# Sheet_24V_PWR.net
KiCad netlist of a schematic drawn in Altium Designer
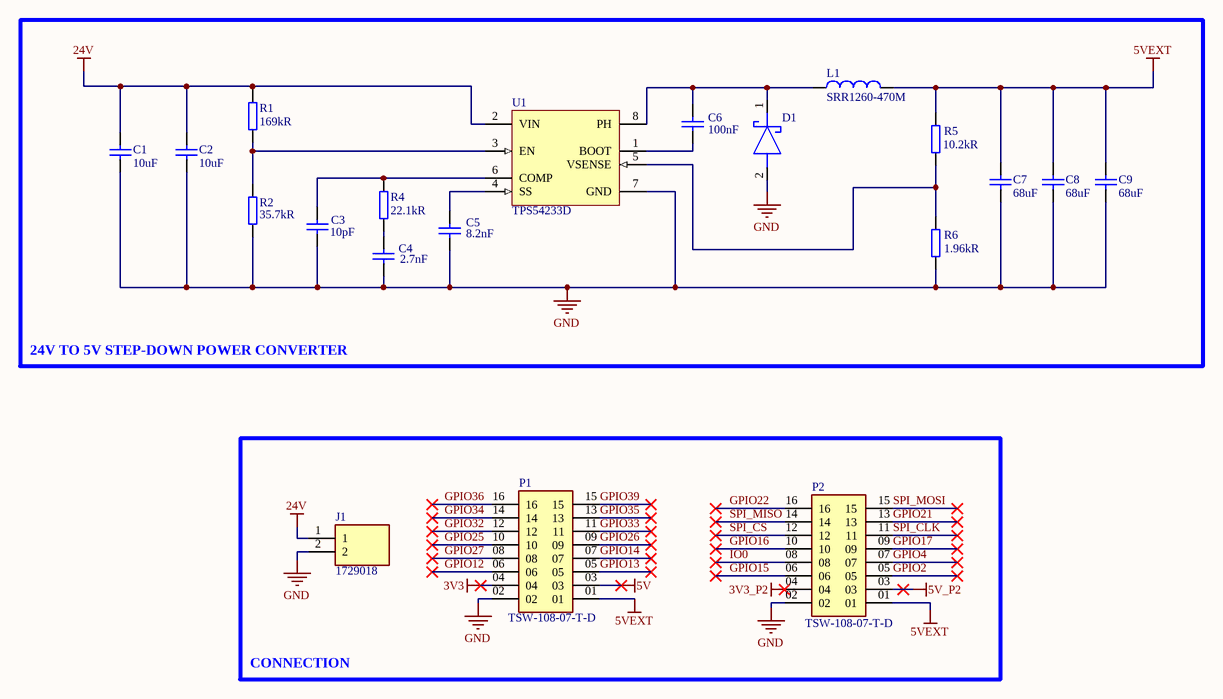
[diagram p0: Sheet_24V_PWR.SchDoc]

(export (version "E")
  (design (tool "Eeschema 10.0.6"))
  (components
    (comp (ref "C1")
      (value "C1210C106M5RACTU")
      (footprint "FP-C3225-250-0_4-IPC_A")
      (description "3225 C 10uF Ceramic Multilayer Capacitor; 50 V; +85degC; X7R Dielectric; +/-20%")
      (fields
        (field (name "MANUFACTURER") "KEMET")
        (field (name "CAPACITANCE") "10uF")
        (field (name "VOLTAGE") "50V")
      )
      (libsource (lib "Schlib1") (part "C1210C106M5RACTU"))
    )
    (comp (ref "C2")
      (value "C1210C106M5RACTU")
      (footprint "FP-C3225-250-0_4-IPC_A")
      (description "3225 C 10uF Ceramic Multilayer Capacitor; 50 V; +85degC; X7R Dielectric; +/-20%")
      (fields
        (field (name "MANUFACTURER") "KEMET")
        (field (name "CAPACITANCE") "10uF")
        (field (name "VOLTAGE") "50V")
      )
      (libsource (lib "Schlib1") (part "C1210C106M5RACTU"))
    )
    (comp (ref "C3")
      (value "C0805C100J5GACTU")
      (footprint "FP-C0805C-DN-IPC_A")
      (description "Cap Ceramic 10pF 50V C0G 5% SMD 0805 125C Plastic T/R")
      (fields
        (field (name "MANUFACTURER") "KEMET")
        (field (name "CAPACITANCE") "10pF")
        (field (name "TOLERANCE") "5%")
      )
      (libsource (lib "Schlib1") (part "C0805C100J5GACTU"))
    )
    (comp (ref "C4")
      (value "C2012C0G1H272J060AA")
      (footprint "FP-C2012-060-0_2-IPC_A")
      (description "Cap Ceramic 0.0027uF 50V C0G 5% SMD 0805 125C Paper T/R")
      (fields
        (field (name "MANUFACTURER") "TDK")
        (field (name "CAPACITANCE") "2.7nF")
        (field (name "TOLERANCE") "5%")
      )
      (libsource (lib "Schlib1") (part "C2012C0G1H272J060AA"))
    )
    (comp (ref "C5")
      (value "C0805C822K4RACTU")
      (footprint "FP-C0805C-DN-IPC_A")
      (description "Capacitor, Ceramic, 8.2nF, 16VDC, 10-% Tol, 10+% Tol, X7R-TC Code, -15, 15%-TC RoHS Compliant: Yes")
      (fields
        (field (name "MANUFACTURER") "KEMET")
        (field (name "CAPACITANCE") "8.2nF")
        (field (name "TOLERANCE") "10%")
      )
      (libsource (lib "Schlib1") (part "C0805C822K4RACTU"))
    )
    (comp (ref "C6")
      (value "C0805C104K8RACTU")
      (footprint "FP-C0805C-DN-IPC_A")
      (description "Cap Ceramic 0.1uF 10V X7R 10% SMD 0805 125°C Paper T/R")
      (fields
        (field (name "MANUFACTURER") "KEMET")
        (field (name "CAPACITANCE") "100nF")
        (field (name "TOLERANCE") "10%")
      )
      (libsource (lib "Schlib1") (part "C0805C104K8RACTU"))
    )
    (comp (ref "C7")
      (value "C3216X5R1A686M160AC")
      (footprint "FP-C3216-160-0_3-IPC_A")
      (description "C Series 1206 68 uF 10 V ±20 % Tolerance X5R SMT Multilayer Ceramic Capacitor")
      (fields
        (field (name "MANUFACTURER") "TDK")
        (field (name "CAPACITANCE") "68uF")
        (field (name "TOLERANCE") "20%")
      )
      (libsource (lib "Schlib1") (part "C3216X5R1A686M160AC"))
    )
    (comp (ref "C8")
      (value "C3216X5R1A686M160AC")
      (footprint "FP-C3216-160-0_3-IPC_A")
      (description "C Series 1206 68 uF 10 V ±20 % Tolerance X5R SMT Multilayer Ceramic Capacitor")
      (fields
        (field (name "MANUFACTURER") "TDK")
        (field (name "CAPACITANCE") "68uF")
        (field (name "TOLERANCE") "20%")
      )
      (libsource (lib "Schlib1") (part "C3216X5R1A686M160AC"))
    )
    (comp (ref "C9")
      (value "C3216X5R1A686M160AC")
      (footprint "FP-C3216-160-0_3-IPC_A")
      (description "C Series 1206 68 uF 10 V ±20 % Tolerance X5R SMT Multilayer Ceramic Capacitor")
      (fields
        (field (name "MANUFACTURER") "TDK")
        (field (name "CAPACITANCE") "68uF")
        (field (name "TOLERANCE") "20%")
      )
      (libsource (lib "Schlib1") (part "C3216X5R1A686M160AC"))
    )
    (comp (ref "D1")
      (value "SS2PH10-M3/84A")
      (footprint "DO-220AA")
      (description "DIODE SCHOTTKY 100V 2A DO220AA")
      (fields (field (name "MANUFACTURER") "Vishay"))
      (libsource (lib "Schlib1") (part "SS2PH10-M3/84A"))
    )
    (comp (ref "J1")
      (value "1729018")
      (footprint "1729018")
      (description "间距5mm 2pin 10A 300V 可拼接 螺钉式 直插")
      (fields (field (name "MANUFACTURER") "Phoenix Contact") (field (name "VOLTAGE") "300V"))
      (libsource (lib "Schlib1") (part "1729018"))
    )
    (comp (ref "L1")
      (value "SRR1260-470M")
      (footprint "SRR1260470M")
      (description "Inductor Power Shielded Wirewound 47uH 20% 100KHz 22Q-Factor Ferrite 2.6A 86mOhm DCR T/R")
      (fields (field (name "MANUFACTURER") "Bourns") (field (name "TOLERANCE") "20%"))
      (libsource (lib "Schlib1") (part "SRR1260-470M"))
    )
    (comp (ref "P1")
      (value "TSW-108-07-T-D")
      (footprint "SAMTEC_TSW-108-07-T-D")
      (description "Conn Unshrouded Header HDR 16 POS 2.54mm Solder ST Thru-Hole Bulk")
      (fields (field (name "MANUFACTURER") "Samtec"))
      (libsource (lib "Schlib1") (part "TSW-108-07-T-D"))
    )
    (comp (ref "P2")
      (value "TSW-108-07-T-D")
      (footprint "SAMTEC_TSW-108-07-T-D")
      (description "Conn Unshrouded Header HDR 16 POS 2.54mm Solder ST Thru-Hole Bulk")
      (fields (field (name "MANUFACTURER") "Samtec"))
      (libsource (lib "Schlib1") (part "TSW-108-07-T-D"))
    )
    (comp (ref "R1")
      (value "ERJ-6ENF1693V")
      (footprint "RESC2013X70X40LL20T20")
      (description "Res Thick Film 0805 169K Ohm 1% 1/8W ±100ppm/°C Molded SMD Punched Carrier T/R")
      (fields
        (field (name "MANUFACTURER") "Panasonic")
        (field (name "RESISTANCE") "169kR")
        (field (name "TOLERANCE") "1%")
      )
      (libsource (lib "Schlib1") (part "ERJ-6ENF1693V"))
    )
    (comp (ref "R2")
      (value "CR0805-FX-3572ELF")
      (footprint "RESC0805(2012)_L")
      (description "Res Thick Film 0805 35.7K Ohm 1% 1/8W 100ppm/C Molded SMD SMD Paper Tape on Plastic Reel")
      (fields
        (field (name "MANUFACTURER") "Bourns")
        (field (name "RESISTANCE") "35.7kR")
        (field (name "TOLERANCE") "1%")
      )
      (libsource (lib "Schlib1") (part "CR0805-FX-3572ELF"))
    )
    (comp (ref "R4")
      (value "CR0805-FX-2212ELF")
      (footprint "RESC2012X60N")
      (description "Res Thick Film 0805 22.1K Ohm 1% 1/8W ±100ppm/°C Molded SMD SMD Paper Tape on Plastic Reel")
      (fields
        (field (name "MANUFACTURER") "Bourns")
        (field (name "RESISTANCE") "22.1kR")
        (field (name "TOLERANCE") "1%")
      )
      (libsource (lib "Schlib1") (part "CR0805-FX-2212ELF"))
    )
    (comp (ref "R5")
      (value "CR0805-FX-1022ELF")
      (footprint "RESC2012X60N")
      (description "Res Thick Film 0805 10.2K Ohm 1% 1/8W ±100ppm/°C Molded SMD SMD Paper Tape on Plastic Reel")
      (fields
        (field (name "MANUFACTURER") "Bourns")
        (field (name "RESISTANCE") "10.2kR")
        (field (name "TOLERANCE") "1%")
      )
      (libsource (lib "Schlib1") (part "CR0805-FX-1022ELF"))
    )
    (comp (ref "R6")
      (value "CRCW08051K96FKEA")
      (footprint "RESC2013X50X30LL20T20")
      (description "Res Thick Film 0805 1.96K Ohm 1% 1/8W ±100ppm/°C Molded SMD SMD Paper T/R")
      (fields
        (field (name "MANUFACTURER") "Vishay")
        (field (name "RESISTANCE") "1.96kR")
        (field (name "TOLERANCE") "1%")
      )
      (libsource (lib "Schlib1") (part "CRCW08051K96FKEA"))
    )
    (comp (ref "U1")
      (value "TPS54233D")
      (footprint "D0008A_L")
      (description "3.5 to 28V Input, 2A, 300kHz Step-Down Converter with Eco-mode 8-SOIC -40 to 150")
      (fields (field (name "MANUFACTURER") "Texas Instruments"))
      (libsource (lib "Schlib1") (part "TPS54233D"))
    )
  )
  (nets
    (net (code "1") (name "/GPIO2") (class "Default")
      (node (ref "P2") (pin "05") (pinfunction "05_05") (pintype "passive+no_connect"))
    )
    (net (code "2") (name "/GPIO4") (class "Default")
      (node (ref "P2") (pin "07") (pinfunction "07_07") (pintype "passive+no_connect"))
    )
    (net (code "3") (name "/GPIO12") (class "Default")
      (node (ref "P1") (pin "06") (pinfunction "06_06") (pintype "passive+no_connect"))
    )
    (net (code "4") (name "/GPIO13") (class "Default")
      (node (ref "P1") (pin "05") (pinfunction "05_05") (pintype "passive+no_connect"))
    )
    (net (code "5") (name "/GPIO14") (class "Default")
      (node (ref "P1") (pin "07") (pinfunction "07_07") (pintype "passive+no_connect"))
    )
    (net (code "6") (name "/GPIO15") (class "Default")
      (node (ref "P2") (pin "06") (pinfunction "06_06") (pintype "passive+no_connect"))
    )
    (net (code "7") (name "/GPIO16") (class "Default")
      (node (ref "P2") (pin "10") (pinfunction "10_10") (pintype "passive+no_connect"))
    )
    (net (code "8") (name "/GPIO17") (class "Default")
      (node (ref "P2") (pin "09") (pinfunction "09_09") (pintype "passive+no_connect"))
    )
    (net (code "9") (name "/GPIO21") (class "Default")
      (node (ref "P2") (pin "13") (pinfunction "13_13") (pintype "passive+no_connect"))
    )
    (net (code "10") (name "/GPIO22") (class "Default")
      (node (ref "P2") (pin "16") (pinfunction "16_16") (pintype "passive+no_connect"))
    )
    (net (code "11") (name "/GPIO25") (class "Default")
      (node (ref "P1") (pin "10") (pinfunction "10_10") (pintype "passive+no_connect"))
    )
    (net (code "12") (name "/GPIO26") (class "Default")
      (node (ref "P1") (pin "09") (pinfunction "09_09") (pintype "passive+no_connect"))
    )
    (net (code "13") (name "/GPIO27") (class "Default")
      (node (ref "P1") (pin "08") (pinfunction "08_08") (pintype "passive+no_connect"))
    )
    (net (code "14") (name "/GPIO32") (class "Default")
      (node (ref "P1") (pin "12") (pinfunction "12_12") (pintype "passive+no_connect"))
    )
    (net (code "15") (name "/GPIO33") (class "Default")
      (node (ref "P1") (pin "11") (pinfunction "11_11") (pintype "passive+no_connect"))
    )
    (net (code "16") (name "/GPIO34") (class "Default")
      (node (ref "P1") (pin "14") (pinfunction "14_14") (pintype "passive+no_connect"))
    )
    (net (code "17") (name "/GPIO35") (class "Default")
      (node (ref "P1") (pin "13") (pinfunction "13_13") (pintype "passive+no_connect"))
    )
    (net (code "18") (name "/GPIO36") (class "Default")
      (node (ref "P1") (pin "16") (pinfunction "16_16") (pintype "passive+no_connect"))
    )
    (net (code "19") (name "/GPIO39") (class "Default")
      (node (ref "P1") (pin "15") (pinfunction "15_15") (pintype "passive+no_connect"))
    )
    (net (code "20") (name "/IO0") (class "Default")
      (node (ref "P2") (pin "08") (pinfunction "08_08") (pintype "passive+no_connect"))
    )
    (net (code "21") (name "/SPI_CLK") (class "Default")
      (node (ref "P2") (pin "11") (pinfunction "11_11") (pintype "passive+no_connect"))
    )
    (net (code "22") (name "/SPI_CS") (class "Default")
      (node (ref "P2") (pin "12") (pinfunction "12_12") (pintype "passive+no_connect"))
    )
    (net (code "23") (name "/SPI_MISO") (class "Default")
      (node (ref "P2") (pin "14") (pinfunction "14_14") (pintype "passive+no_connect"))
    )
    (net (code "24") (name "/SPI_MOSI") (class "Default")
      (node (ref "P2") (pin "15") (pinfunction "15_15") (pintype "passive+no_connect"))
    )
    (net (code "25") (name "3V3") (class "Default")
      (node (ref "P1") (pin "04") (pinfunction "04_04") (pintype "passive"))
    )
    (net (code "26") (name "3V3_P2") (class "Default")
      (node (ref "P2") (pin "04") (pinfunction "04_04") (pintype "passive"))
    )
    (net (code "27") (name "5V") (class "Default")
      (node (ref "P1") (pin "03") (pinfunction "03_03") (pintype "passive"))
    )
    (net (code "28") (name "5VEXT") (class "Default")
      (node (ref "C7") (pin "1") (pinfunction "1_1") (pintype "passive"))
      (node (ref "C8") (pin "1") (pinfunction "1_1") (pintype "passive"))
      (node (ref "C9") (pin "1") (pinfunction "1_1") (pintype "passive"))
      (node (ref "L1") (pin "2") (pinfunction "2_2") (pintype "passive"))
      (node (ref "P1") (pin "01") (pinfunction "01_01") (pintype "passive"))
      (node (ref "P2") (pin "01") (pinfunction "01_01") (pintype "passive"))
      (node (ref "R5") (pin "1") (pinfunction "1_1") (pintype "passive"))
    )
    (net (code "29") (name "5V_P2") (class "Default")
      (node (ref "P2") (pin "03") (pinfunction "03_03") (pintype "passive"))
    )
    (net (code "30") (name "24V") (class "Default")
      (node (ref "C1") (pin "1") (pinfunction "1_1") (pintype "passive"))
      (node (ref "C2") (pin "1") (pinfunction "1_1") (pintype "passive"))
      (node (ref "J1") (pin "1") (pinfunction "1_1") (pintype "passive"))
      (node (ref "R1") (pin "1") (pinfunction "1_1") (pintype "passive"))
      (node (ref "U1") (pin "2") (pinfunction "VIN_2") (pintype "power_in"))
    )
    (net (code "31") (name "GND") (class "Default")
      (node (ref "C1") (pin "2") (pinfunction "2_2") (pintype "passive"))
      (node (ref "C2") (pin "2") (pinfunction "2_2") (pintype "passive"))
      (node (ref "C3") (pin "2") (pinfunction "2_2") (pintype "passive"))
      (node (ref "C4") (pin "2") (pinfunction "2_2") (pintype "passive"))
      (node (ref "C5") (pin "2") (pinfunction "2_2") (pintype "passive"))
      (node (ref "C7") (pin "2") (pinfunction "2_2") (pintype "passive"))
      (node (ref "C8") (pin "2") (pinfunction "2_2") (pintype "passive"))
      (node (ref "C9") (pin "2") (pinfunction "2_2") (pintype "passive"))
      (node (ref "D1") (pin "2") (pinfunction "A_2") (pintype "passive"))
      (node (ref "J1") (pin "2") (pinfunction "2_2") (pintype "passive"))
      (node (ref "P1") (pin "02") (pinfunction "02_02") (pintype "passive"))
      (node (ref "P2") (pin "02") (pinfunction "02_02") (pintype "passive"))
      (node (ref "R2") (pin "2") (pinfunction "2_2") (pintype "passive"))
      (node (ref "R6") (pin "2") (pinfunction "2_2") (pintype "passive"))
      (node (ref "U1") (pin "7") (pinfunction "GND_7") (pintype "power_in"))
    )
    (net (code "32") (name "Net-(C4-Pad1)") (class "Default")
      (node (ref "C4") (pin "1") (pinfunction "1_1") (pintype "passive"))
      (node (ref "R4") (pin "2") (pinfunction "2_2") (pintype "passive"))
    )
    (net (code "33") (name "Net-(D1-K)") (class "Default")
      (node (ref "C6") (pin "1") (pinfunction "1_1") (pintype "passive"))
      (node (ref "D1") (pin "1") (pinfunction "K_1") (pintype "passive"))
      (node (ref "L1") (pin "1") (pinfunction "1_1") (pintype "passive"))
      (node (ref "U1") (pin "8") (pinfunction "PH_8") (pintype "power_in"))
    )
    (net (code "34") (name "Net-(U1-BOOT)") (class "Default")
      (node (ref "C6") (pin "2") (pinfunction "2_2") (pintype "passive"))
      (node (ref "U1") (pin "1") (pinfunction "BOOT_1") (pintype "passive"))
    )
    (net (code "35") (name "Net-(U1-COMP)") (class "Default")
      (node (ref "C3") (pin "1") (pinfunction "1_1") (pintype "passive"))
      (node (ref "R4") (pin "1") (pinfunction "1_1") (pintype "passive"))
      (node (ref "U1") (pin "6") (pinfunction "COMP_6") (pintype "passive"))
    )
    (net (code "36") (name "Net-(U1-EN)") (class "Default")
      (node (ref "R1") (pin "2") (pinfunction "2_2") (pintype "passive"))
      (node (ref "R2") (pin "1") (pinfunction "1_1") (pintype "passive"))
      (node (ref "U1") (pin "3") (pinfunction "EN_3") (pintype "input"))
    )
    (net (code "37") (name "Net-(U1-SS)") (class "Default")
      (node (ref "C5") (pin "1") (pinfunction "1_1") (pintype "passive"))
      (node (ref "U1") (pin "4") (pinfunction "SS_4") (pintype "input"))
    )
    (net (code "38") (name "Net-(U1-VSENSE)") (class "Default")
      (node (ref "R5") (pin "2") (pinfunction "2_2") (pintype "passive"))
      (node (ref "R6") (pin "1") (pinfunction "1_1") (pintype "passive"))
      (node (ref "U1") (pin "5") (pinfunction "VSENSE_5") (pintype "input"))
    )
  )
)
